# bbr18_ball_sensor_board.net
KiCad netlist of a schematic drawn in Altium Designer
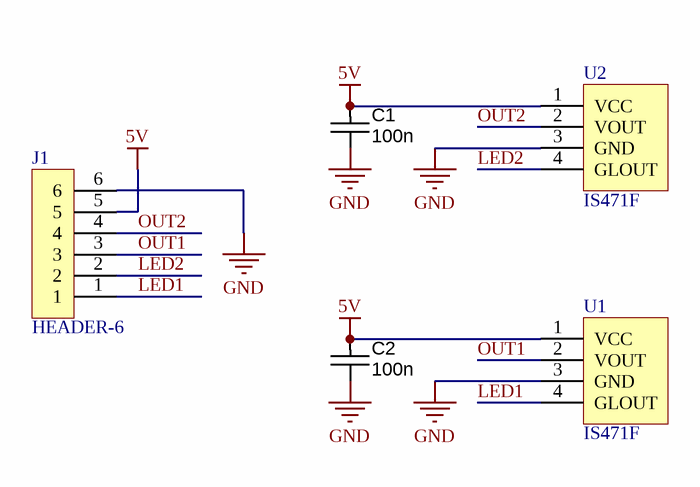
[diagram p0: bbr18_ball_sensor_board.SchDoc]

(export (version "E")
  (design (tool "Eeschema 10.0.6"))
  (components
    (comp (ref "C1")
      (value "100n")
      (footprint "CAPC1608X90N")
      (description "Capacitor SMD Cer 100nF 10% 50V X7R 0603")
      (fields (field (name "TOLERANCE") "±10%"))
      (libsource (lib "PBL - Capacitors") (part "CAPC_100n_0603_X7R_50V_10%"))
    )
    (comp (ref "C2")
      (value "100n")
      (footprint "CAPC1608X90N")
      (description "Capacitor SMD Cer 100nF 10% 50V X7R 0603")
      (fields (field (name "TOLERANCE") "±10%"))
      (libsource (lib "PBL - Capacitors") (part "CAPC_100n_0603_X7R_50V_10%"))
    )
    (comp (ref "J1")
      (value "HEADER-6")
      (footprint "MICRO-MATCH-MOB-06")
      (libsource (lib "connectors_micromatch") (part "HEADER-6"))
    )
    (comp (ref "U1") (value "IS471F") (footprint "IS471F") (libsource (lib "misc") (part "IS471F")))
    (comp (ref "U2") (value "IS471F") (footprint "IS471F") (libsource (lib "misc") (part "IS471F")))
  )
  (nets
    (net (code "1") (name "/LED1") (class "Default")
      (node (ref "J1") (pin "1") (pinfunction "1_1") (pintype "passive"))
      (node (ref "U1") (pin "4") (pinfunction "GLOUT_4") (pintype "passive"))
    )
    (net (code "2") (name "/LED2") (class "Default")
      (node (ref "J1") (pin "2") (pinfunction "2_2") (pintype "passive"))
      (node (ref "U2") (pin "4") (pinfunction "GLOUT_4") (pintype "passive"))
    )
    (net (code "3") (name "/OUT1") (class "Default")
      (node (ref "J1") (pin "3") (pinfunction "3_3") (pintype "passive"))
      (node (ref "U1") (pin "2") (pinfunction "VOUT_2") (pintype "passive"))
    )
    (net (code "4") (name "/OUT2") (class "Default")
      (node (ref "J1") (pin "4") (pinfunction "4_4") (pintype "passive"))
      (node (ref "U2") (pin "2") (pinfunction "VOUT_2") (pintype "passive"))
    )
    (net (code "5") (name "5V") (class "Default")
      (node (ref "C1") (pin "1") (pintype "passive"))
      (node (ref "C2") (pin "1") (pintype "passive"))
      (node (ref "J1") (pin "5") (pinfunction "5_5") (pintype "passive"))
      (node (ref "U1") (pin "1") (pinfunction "VCC_1") (pintype "passive"))
      (node (ref "U2") (pin "1") (pinfunction "VCC_1") (pintype "passive"))
    )
    (net (code "6") (name "GND") (class "Default")
      (node (ref "C1") (pin "2") (pintype "passive"))
      (node (ref "C2") (pin "2") (pintype "passive"))
      (node (ref "J1") (pin "6") (pinfunction "6_6") (pintype "passive"))
      (node (ref "U1") (pin "3") (pinfunction "GND_3") (pintype "passive"))
      (node (ref "U2") (pin "3") (pinfunction "GND_3") (pintype "passive"))
    )
  )
)
